# Master_V0_1.net
KiCad netlist of a schematic drawn in EAGLE
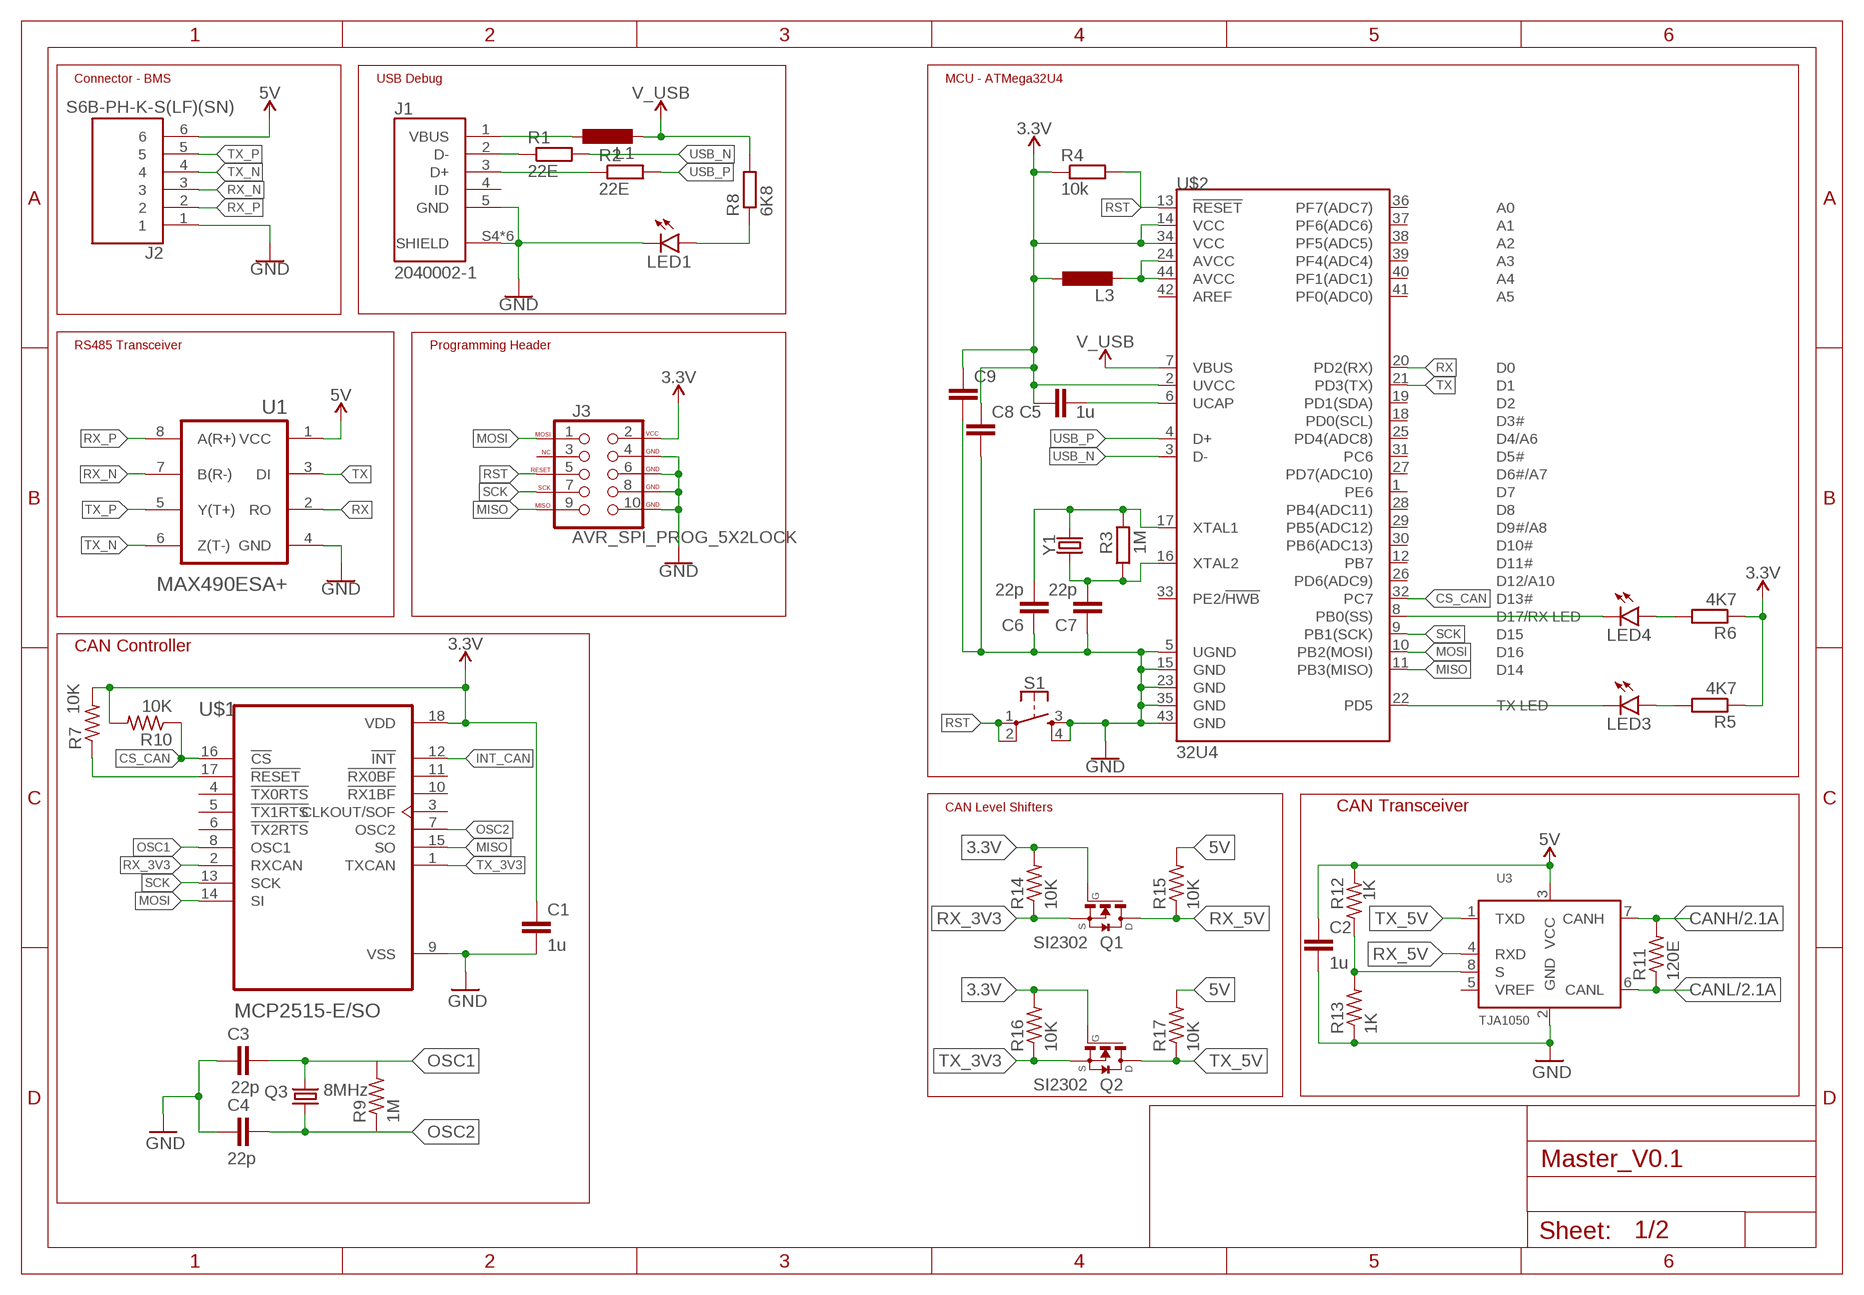
[diagram p0: schematic, sheet 1]
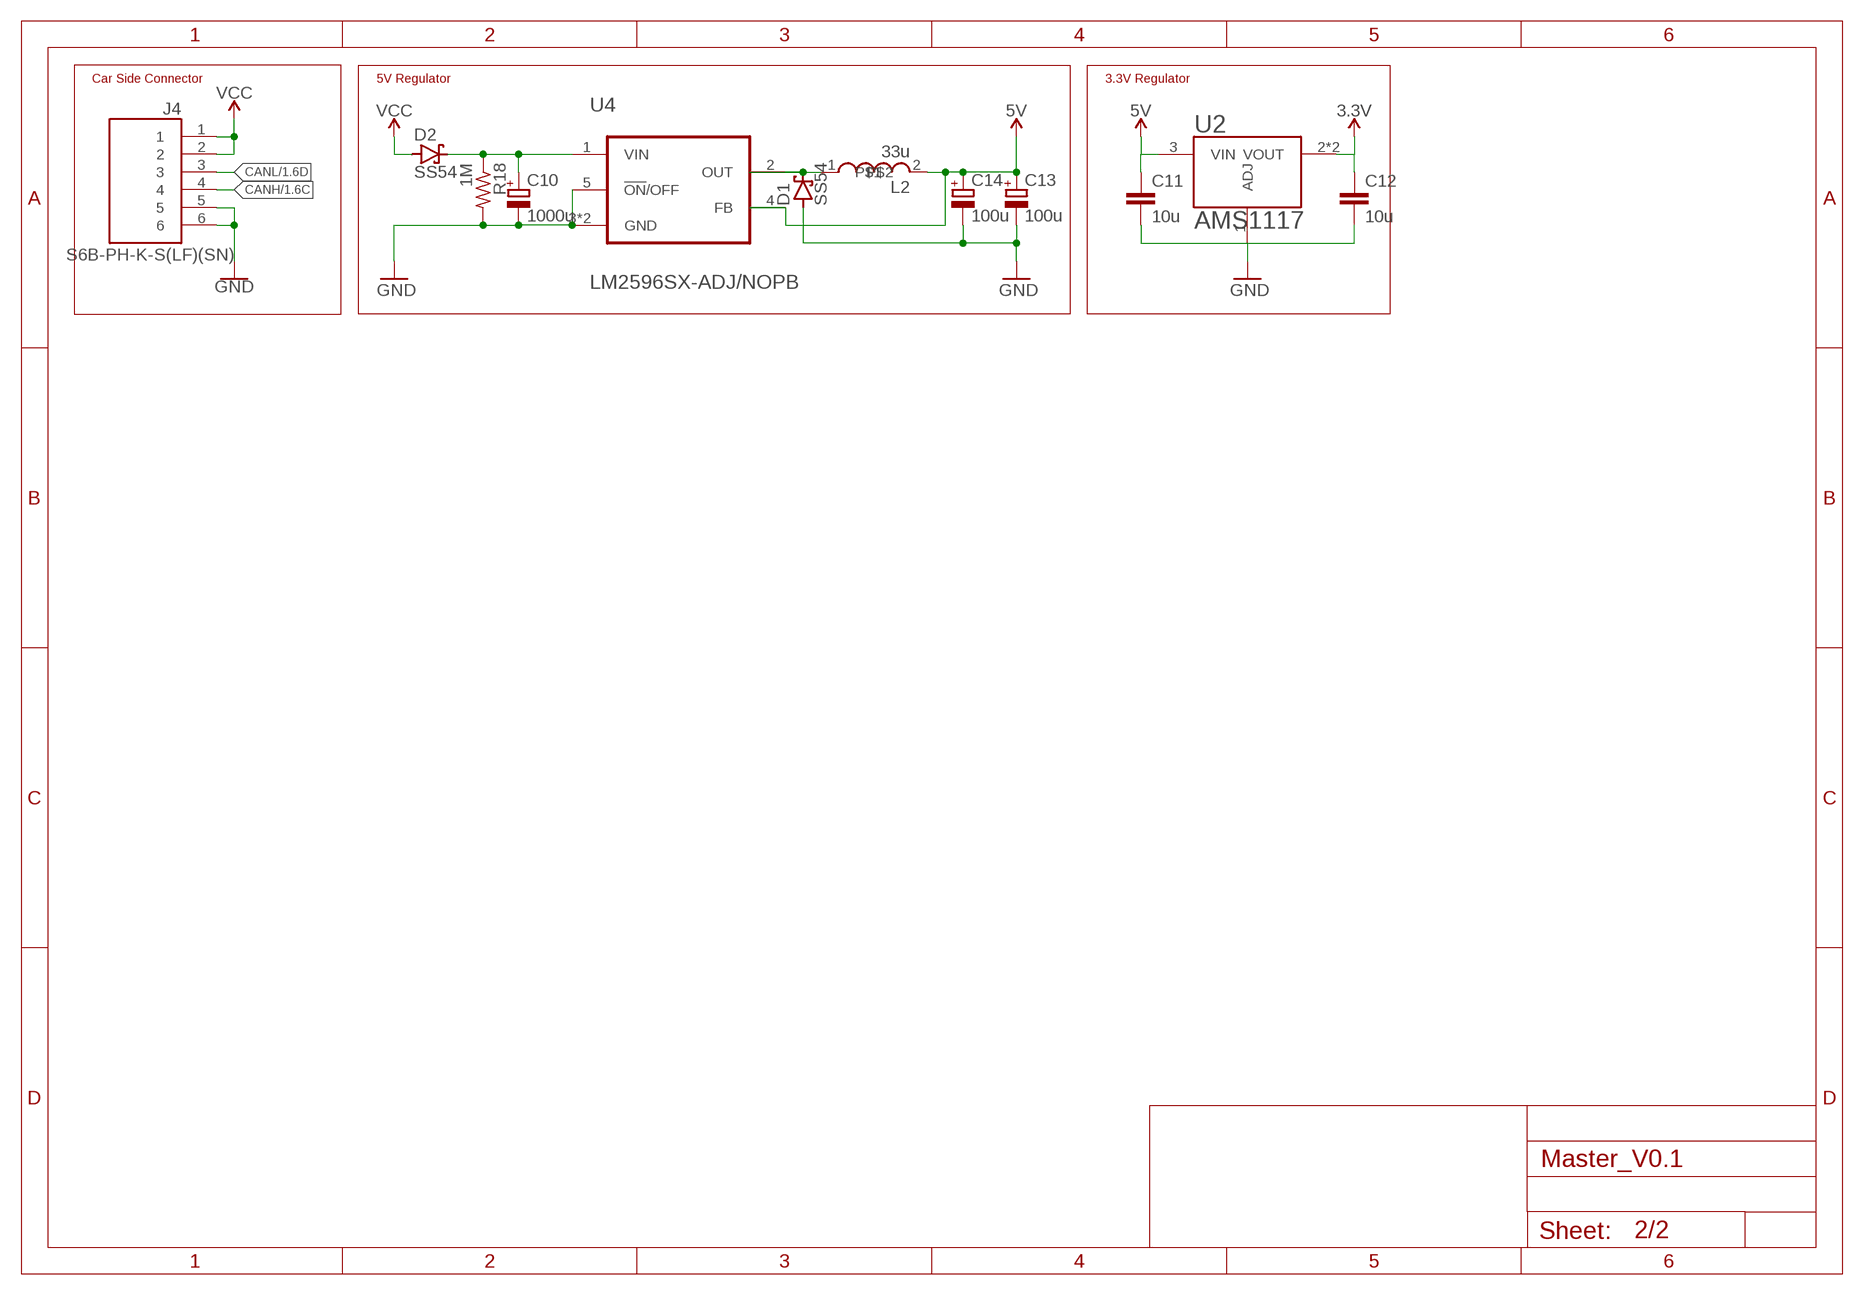
[diagram p1: schematic, sheet 2]

(export (version "E")
  (design (tool "Eeschema 10.0.6"))
  (components
    (comp (ref "C1")
      (value "1u")
      (footprint "eagle-import:C0805")
      (libsource (lib "eagle-import") (part "C-EUC0805"))
    )
    (comp (ref "C2")
      (value "1u")
      (footprint "eagle-import:C0805")
      (libsource (lib "eagle-import") (part "C-EUC0805"))
    )
    (comp (ref "C3")
      (value "22p")
      (footprint "eagle-import:C0805")
      (libsource (lib "eagle-import") (part "C-EUC0805"))
    )
    (comp (ref "C4")
      (value "22p")
      (footprint "eagle-import:C0805")
      (libsource (lib "eagle-import") (part "C-EUC0805"))
    )
    (comp (ref "C5")
      (value "1u")
      (footprint "eagle-import:C0805")
      (libsource (lib "eagle-import") (part "C-EUC0805"))
    )
    (comp (ref "C6")
      (value "22p")
      (footprint "eagle-import:C0805")
      (libsource (lib "eagle-import") (part "C-EUC0805"))
    )
    (comp (ref "C7")
      (value "22p")
      (footprint "eagle-import:C0805")
      (libsource (lib "eagle-import") (part "C-EUC0805"))
    )
    (comp (ref "C8")
      (value "C-EUC0805")
      (footprint "eagle-import:C0805")
      (libsource (lib "eagle-import") (part "C-EUC0805"))
    )
    (comp (ref "C9")
      (value "C-EUC0805")
      (footprint "eagle-import:C0805")
      (libsource (lib "eagle-import") (part "C-EUC0805"))
    )
    (comp (ref "J1")
      (value "2040002-1")
      (footprint "eagle-import:TE_2040002-1")
      (fields (field (name "MF") "TE Connectivity"))
      (libsource (lib "eagle-import") (part "2040002-1"))
    )
    (comp (ref "J2")
      (value "S6B-PH-K-S(LF)(SN)")
      (footprint "eagle-import:JST_S6B-PH-K-S(LF)(SN)")
      (fields (field (name "MF") "JST Sales"))
      (libsource (lib "eagle-import") (part "S6B-PH-K-S(LF)(SN)"))
    )
    (comp (ref "J3")
      (value "AVR_SPI_PROG_5X2LOCK")
      (footprint "eagle-import:2X5-SHROUDED_LOCK")
      (libsource (lib "eagle-import") (part "AVR_SPI_PROG_5X2LOCK"))
    )
    (comp (ref "L1")
      (value "L-EUL2012C")
      (footprint "eagle-import:L2012C")
      (libsource (lib "eagle-import") (part "L-EUL2012C"))
    )
    (comp (ref "L3")
      (value "L-EUL2012C")
      (footprint "eagle-import:L2012C")
      (libsource (lib "eagle-import") (part "L-EUL2012C"))
    )
    (comp (ref "LED1")
      (value "LEDCHIPLED_0805")
      (footprint "eagle-import:CHIPLED_0805")
      (libsource (lib "eagle-import") (part "LEDCHIPLED_0805"))
    )
    (comp (ref "LED3")
      (value "LEDCHIPLED_0805")
      (footprint "eagle-import:CHIPLED_0805")
      (libsource (lib "eagle-import") (part "LEDCHIPLED_0805"))
    )
    (comp (ref "LED4")
      (value "LEDCHIPLED_0805")
      (footprint "eagle-import:CHIPLED_0805")
      (libsource (lib "eagle-import") (part "LEDCHIPLED_0805"))
    )
    (comp (ref "Q1")
      (value "SI2302")
      (footprint "eagle-import:SOT23")
      (fields (field (name "MF") "Vishay Siliconix"))
      (libsource (lib "eagle-import") (part "SI2302"))
    )
    (comp (ref "Q2")
      (value "SI2302")
      (footprint "eagle-import:SOT23")
      (fields (field (name "MF") "Vishay Siliconix"))
      (libsource (lib "eagle-import") (part "SI2302"))
    )
    (comp (ref "Q3")
      (value "8MHz")
      (footprint "eagle-import:HC49_S")
      (libsource (lib "eagle-import") (part "CRYSTALHC49S"))
    )
    (comp (ref "R1")
      (value "22E")
      (footprint "eagle-import:R0805")
      (libsource (lib "eagle-import") (part "R-EU_R0805"))
    )
    (comp (ref "R2")
      (value "22E")
      (footprint "eagle-import:R0805")
      (libsource (lib "eagle-import") (part "R-EU_R0805"))
    )
    (comp (ref "R3")
      (value "1M")
      (footprint "eagle-import:R0805")
      (libsource (lib "eagle-import") (part "R-EU_R0805"))
    )
    (comp (ref "R4")
      (value "10k")
      (footprint "eagle-import:R0805")
      (libsource (lib "eagle-import") (part "R-EU_R0805"))
    )
    (comp (ref "R5")
      (value "4K7")
      (footprint "eagle-import:R0805")
      (libsource (lib "eagle-import") (part "R-EU_R0805"))
    )
    (comp (ref "R6")
      (value "4K7")
      (footprint "eagle-import:R0805")
      (libsource (lib "eagle-import") (part "R-EU_R0805"))
    )
    (comp (ref "R7")
      (value "10K")
      (footprint "eagle-import:R0805")
      (libsource (lib "eagle-import") (part "R-US_R0805"))
    )
    (comp (ref "R8")
      (value "6K8")
      (footprint "eagle-import:R0805")
      (libsource (lib "eagle-import") (part "R-EU_R0805"))
    )
    (comp (ref "R9")
      (value "1M")
      (footprint "eagle-import:R0805")
      (libsource (lib "eagle-import") (part "R-US_R0805"))
    )
    (comp (ref "R10")
      (value "10K")
      (footprint "eagle-import:R0805")
      (libsource (lib "eagle-import") (part "R-US_R0805"))
    )
    (comp (ref "R11")
      (value "120E")
      (footprint "eagle-import:R0805")
      (libsource (lib "eagle-import") (part "R-US_R0805"))
    )
    (comp (ref "R12")
      (value "1K")
      (footprint "eagle-import:R0805")
      (libsource (lib "eagle-import") (part "R-US_R0805"))
    )
    (comp (ref "R13")
      (value "1K")
      (footprint "eagle-import:R0805")
      (libsource (lib "eagle-import") (part "R-US_R0805"))
    )
    (comp (ref "R14")
      (value "10K")
      (footprint "eagle-import:R0805")
      (libsource (lib "eagle-import") (part "R-US_R0805"))
    )
    (comp (ref "R15")
      (value "10K")
      (footprint "eagle-import:R0805")
      (libsource (lib "eagle-import") (part "R-US_R0805"))
    )
    (comp (ref "R16")
      (value "10K")
      (footprint "eagle-import:R0805")
      (libsource (lib "eagle-import") (part "R-US_R0805"))
    )
    (comp (ref "R17")
      (value "10K")
      (footprint "eagle-import:R0805")
      (libsource (lib "eagle-import") (part "R-US_R0805"))
    )
    (comp (ref "S1")
      (value "MOMENTARY-SWITCH-SPST-2-SMD-5.2MM")
      (footprint "eagle-import:TACTILE_SWITCH_SMD_5.2MM")
      (libsource (lib "eagle-import") (part "MOMENTARY-SWITCH-SPST-2-SMD-5.2MM"))
    )
    (comp (ref "U$1")
      (value "MCP2515-E/SO")
      (footprint "eagle-import:SOIC127P1030X265-18N")
      (fields (field (name "MF") "Microchip"))
      (libsource (lib "eagle-import") (part "MCP2515-E/SO"))
    )
    (comp (ref "U$2")
      (value "32U4")
      (footprint "eagle-import:TQFP44")
      (libsource (lib "eagle-import") (part "ATMEGA32U4TQFP-44"))
    )
    (comp (ref "U1")
      (value "MAX490ESA+")
      (footprint "eagle-import:SOIC127P600X175-8N")
      (fields (field (name "MF") "Maxim Integrated"))
      (libsource (lib "eagle-import") (part "MAX490ESA+"))
    )
    (comp (ref "U3")
      (value "TJA1050")
      (footprint "eagle-import:SOT96-1")
      (fields (field (name "MF") "NXP USA"))
      (libsource (lib "eagle-import") (part "TJA1050"))
    )
    (comp (ref "Y1")
      (value "CRYSTALPTH-HC49UV")
      (footprint "eagle-import:HC49U")
      (libsource (lib "eagle-import") (part "CRYSTALPTH-HC49UV"))
    )
    (comp (ref "C10")
      (value "1000u")
      (footprint "eagle-import:E5-10,5")
      (libsource (lib "eagle-import") (part "CPOL-EUE5-10.5"))
    )
    (comp (ref "C11")
      (value "10u")
      (footprint "eagle-import:C0805")
      (libsource (lib "eagle-import") (part "C-EUC0805"))
    )
    (comp (ref "C12")
      (value "10u")
      (footprint "eagle-import:C0805")
      (libsource (lib "eagle-import") (part "C-EUC0805"))
    )
    (comp (ref "C13")
      (value "100u")
      (footprint "eagle-import:E2-4")
      (libsource (lib "eagle-import") (part "CPOL-EUE2-4"))
    )
    (comp (ref "C14")
      (value "100u")
      (footprint "eagle-import:E2-4")
      (libsource (lib "eagle-import") (part "CPOL-EUE2-4"))
    )
    (comp (ref "D1")
      (value "SS54")
      (footprint "eagle-import:SMC")
      (libsource (lib "eagle-import") (part "SCHOTTKY-DIODESMC"))
    )
    (comp (ref "D2")
      (value "SS54")
      (footprint "eagle-import:SMC")
      (libsource (lib "eagle-import") (part "SCHOTTKY-DIODESMC"))
    )
    (comp (ref "J4")
      (value "S6B-PH-K-S(LF)(SN)")
      (footprint "eagle-import:JST_S6B-PH-K-S(LF)(SN)")
      (fields (field (name "MF") "JST Sales"))
      (libsource (lib "eagle-import") (part "S6B-PH-K-S(LF)(SN)"))
    )
    (comp (ref "L2")
      (value "33u")
      (footprint "eagle-import:CDRH127_LD")
      (libsource (lib "eagle-import") (part "CDRH127/LDCDRH/LD"))
    )
    (comp (ref "R18")
      (value "1M")
      (footprint "eagle-import:R0805")
      (libsource (lib "eagle-import") (part "R-US_R0805"))
    )
    (comp (ref "U2")
      (value "AMS1117")
      (footprint "eagle-import:SOT230P700X170-4")
      (fields (field (name "MF") "Advanced Monolithic Systems, Inc."))
      (libsource (lib "eagle-import") (part "AMS1117"))
    )
    (comp (ref "U4")
      (value "LM2596SX-ADJ/NOPB")
      (footprint "eagle-import:VREG_LM2596SX-ADJ_NOPB")
      (fields (field (name "MF") "Texas Instruments"))
      (libsource (lib "eagle-import") (part "LM2596SX-ADJ/NOPB"))
    )
  )
  (nets
    (net (code "1") (name "3.3V") (class "Default")
      (node (ref "C1") (pin "1") (pinfunction "1_1") (pintype "passive"))
      (node (ref "C12") (pin "1") (pinfunction "1_1") (pintype "passive"))
      (node (ref "C5") (pin "1") (pinfunction "1_1") (pintype "passive"))
      (node (ref "C8") (pin "1") (pinfunction "1_1") (pintype "passive"))
      (node (ref "C9") (pin "1") (pinfunction "1_1") (pintype "passive"))
      (node (ref "J3") (pin "2") (pinfunction "VCC_2") (pintype "power_in"))
      (node (ref "L3") (pin "1") (pinfunction "1_1") (pintype "passive"))
      (node (ref "Q1") (pin "1") (pinfunction "G_1") (pintype "passive"))
      (node (ref "Q2") (pin "1") (pinfunction "G_1") (pintype "passive"))
      (node (ref "R10") (pin "2") (pinfunction "2_2") (pintype "passive"))
      (node (ref "R14") (pin "2") (pinfunction "2_2") (pintype "passive"))
      (node (ref "R16") (pin "2") (pinfunction "2_2") (pintype "passive"))
      (node (ref "R4") (pin "1") (pinfunction "1_1") (pintype "passive"))
      (node (ref "R5") (pin "1") (pinfunction "1_1") (pintype "passive"))
      (node (ref "R6") (pin "1") (pinfunction "1_1") (pintype "passive"))
      (node (ref "R7") (pin "2") (pinfunction "2_2") (pintype "passive"))
      (node (ref "U$1") (pin "18") (pinfunction "VDD_18") (pintype "power_in"))
      (node (ref "U$2") (pin "14") (pinfunction "VCC_14") (pintype "bidirectional"))
      (node (ref "U$2") (pin "2") (pinfunction "UVCC_2") (pintype "bidirectional"))
      (node (ref "U$2") (pin "34") (pinfunction "VCC_34") (pintype "bidirectional"))
      (node (ref "U2") (pin "2") (pinfunction "VOUT_2") (pintype "output"))
      (node (ref "U2") (pin "4") (pinfunction "VOUT_4") (pintype "output"))
    )
    (net (code "2") (name "5V") (class "Default")
      (node (ref "C11") (pin "1") (pinfunction "1_1") (pintype "passive"))
      (node (ref "C13") (pin "+") (pinfunction "+_+") (pintype "passive"))
      (node (ref "C14") (pin "+") (pinfunction "+_+") (pintype "passive"))
      (node (ref "C2") (pin "1") (pinfunction "1_1") (pintype "passive"))
      (node (ref "J2") (pin "6") (pinfunction "6_6") (pintype "passive"))
      (node (ref "L2") (pin "2") (pinfunction "P$2_2") (pintype "bidirectional"))
      (node (ref "R12") (pin "2") (pinfunction "2_2") (pintype "passive"))
      (node (ref "R15") (pin "2") (pinfunction "2_2") (pintype "passive"))
      (node (ref "R17") (pin "2") (pinfunction "2_2") (pintype "passive"))
      (node (ref "U1") (pin "1") (pinfunction "VCC_1") (pintype "power_in"))
      (node (ref "U2") (pin "3") (pinfunction "VIN_3") (pintype "input"))
      (node (ref "U3") (pin "3") (pinfunction "VCC_3") (pintype "bidirectional"))
      (node (ref "U4") (pin "4") (pinfunction "FB_4") (pintype "input"))
    )
    (net (code "3") (name "CANH") (class "Default")
      (node (ref "J4") (pin "4") (pinfunction "4_4") (pintype "passive"))
      (node (ref "R11") (pin "2") (pinfunction "2_2") (pintype "passive"))
      (node (ref "U3") (pin "7") (pinfunction "CANH_7") (pintype "bidirectional"))
    )
    (net (code "4") (name "CANL") (class "Default")
      (node (ref "J4") (pin "3") (pinfunction "3_3") (pintype "passive"))
      (node (ref "R11") (pin "1") (pinfunction "1_1") (pintype "passive"))
      (node (ref "U3") (pin "6") (pinfunction "CANL_6") (pintype "bidirectional"))
    )
    (net (code "5") (name "CS_CAN") (class "Default")
      (node (ref "R10") (pin "1") (pinfunction "1_1") (pintype "passive"))
      (node (ref "U$1") (pin "16") (pinfunction "~{CS}_16") (pintype "input"))
      (node (ref "U$2") (pin "32") (pinfunction "PC7_32") (pintype "bidirectional"))
    )
    (net (code "6") (name "GND") (class "Default")
      (node (ref "C1") (pin "2") (pinfunction "2_2") (pintype "passive"))
      (node (ref "C10") (pin "-") (pinfunction "-_-") (pintype "passive"))
      (node (ref "C11") (pin "2") (pinfunction "2_2") (pintype "passive"))
      (node (ref "C12") (pin "2") (pinfunction "2_2") (pintype "passive"))
      (node (ref "C13") (pin "-") (pinfunction "-_-") (pintype "passive"))
      (node (ref "C14") (pin "-") (pinfunction "-_-") (pintype "passive"))
      (node (ref "C2") (pin "2") (pinfunction "2_2") (pintype "passive"))
      (node (ref "C3") (pin "1") (pinfunction "1_1") (pintype "passive"))
      (node (ref "C4") (pin "1") (pinfunction "1_1") (pintype "passive"))
      (node (ref "C6") (pin "1") (pinfunction "1_1") (pintype "passive"))
      (node (ref "C7") (pin "1") (pinfunction "1_1") (pintype "passive"))
      (node (ref "C8") (pin "2") (pinfunction "2_2") (pintype "passive"))
      (node (ref "C9") (pin "2") (pinfunction "2_2") (pintype "passive"))
      (node (ref "D1") (pin "A") (pinfunction "A_A") (pintype "passive"))
      (node (ref "J1") (pin "5") (pinfunction "GND_5") (pintype "power_in"))
      (node (ref "J1") (pin "S4") (pinfunction "SHIELD_S4") (pintype "power_in"))
      (node (ref "J1") (pin "S5") (pinfunction "SHIELD_S5") (pintype "power_in"))
      (node (ref "J1") (pin "SH1") (pinfunction "SHIELD_SH1") (pintype "power_in"))
      (node (ref "J1") (pin "SH2") (pinfunction "SHIELD_SH2") (pintype "power_in"))
      (node (ref "J1") (pin "SH3") (pinfunction "SHIELD_SH3") (pintype "power_in"))
      (node (ref "J1") (pin "SH4") (pinfunction "SHIELD_SH4") (pintype "power_in"))
      (node (ref "J2") (pin "1") (pinfunction "1_1") (pintype "passive"))
      (node (ref "J3") (pin "10") (pinfunction "GND_10") (pintype "power_in"))
      (node (ref "J3") (pin "4") (pinfunction "GND_4") (pintype "power_in"))
      (node (ref "J3") (pin "6") (pinfunction "GND_6") (pintype "power_in"))
      (node (ref "J3") (pin "8") (pinfunction "GND_8") (pintype "power_in"))
      (node (ref "J4") (pin "5") (pinfunction "5_5") (pintype "passive"))
      (node (ref "J4") (pin "6") (pinfunction "6_6") (pintype "passive"))
      (node (ref "LED1") (pin "C") (pinfunction "C_C") (pintype "passive"))
      (node (ref "R13") (pin "1") (pinfunction "1_1") (pintype "passive"))
      (node (ref "R18") (pin "2") (pinfunction "2_2") (pintype "passive"))
      (node (ref "S1") (pin "3") (pinfunction "3_3") (pintype "passive"))
      (node (ref "S1") (pin "4") (pinfunction "4_4") (pintype "passive"))
      (node (ref "U$1") (pin "9") (pinfunction "VSS_9") (pintype "power_in"))
      (node (ref "U$2") (pin "15") (pinfunction "GND_15") (pintype "bidirectional"))
      (node (ref "U$2") (pin "23") (pinfunction "GND_23") (pintype "bidirectional"))
      (node (ref "U$2") (pin "35") (pinfunction "GND_35") (pintype "bidirectional"))
      (node (ref "U$2") (pin "43") (pinfunction "GND_43") (pintype "bidirectional"))
      (node (ref "U$2") (pin "5") (pinfunction "UGND_5") (pintype "bidirectional"))
      (node (ref "U1") (pin "4") (pinfunction "GND_4") (pintype "power_in"))
      (node (ref "U2") (pin "1") (pinfunction "ADJ_1") (pintype "power_in"))
      (node (ref "U3") (pin "2") (pinfunction "GND_2") (pintype "bidirectional"))
      (node (ref "U4") (pin "3") (pinfunction "GND_3") (pintype "power_in"))
      (node (ref "U4") (pin "5") (pinfunction "~{ON}/OFF_5") (pintype "input"))
      (node (ref "U4") (pin "6") (pinfunction "GND_6") (pintype "power_in"))
    )
    (net (code "7") (name "INT_CAN") (class "Default")
      (node (ref "U$1") (pin "12") (pinfunction "~{INT}_12") (pintype "output"))
    )
    (net (code "8") (name "MISO") (class "Default")
      (node (ref "J3") (pin "9") (pinfunction "MISO_9") (pintype "passive"))
      (node (ref "U$1") (pin "15") (pinfunction "SO_15") (pintype "output"))
      (node (ref "U$2") (pin "11") (pinfunction "PB3(MISO)_11") (pintype "bidirectional"))
    )
    (net (code "9") (name "MOSI") (class "Default")
      (node (ref "J3") (pin "1") (pinfunction "MOSI_1") (pintype "passive"))
      (node (ref "U$1") (pin "14") (pinfunction "SI_14") (pintype "input"))
      (node (ref "U$2") (pin "10") (pinfunction "PB2(MOSI)_10") (pintype "bidirectional"))
    )
    (net (code "10") (name "Net-(J1-D+)") (class "Default")
      (node (ref "J1") (pin "3") (pinfunction "D+_3") (pintype "bidirectional"))
      (node (ref "R2") (pin "1") (pinfunction "1_1") (pintype "passive"))
    )
    (net (code "11") (name "Net-(J1-D-)") (class "Default")
      (node (ref "J1") (pin "2") (pinfunction "D-_2") (pintype "bidirectional"))
      (node (ref "R1") (pin "1") (pinfunction "1_1") (pintype "passive"))
    )
    (net (code "12") (name "Net-(J1-VBUS)") (class "Default")
      (node (ref "J1") (pin "1") (pinfunction "VBUS_1") (pintype "power_in"))
      (node (ref "L1") (pin "1") (pinfunction "1_1") (pintype "passive"))
    )
    (net (code "13") (name "Net-(L2-P$1)") (class "Default")
      (node (ref "D1") (pin "C") (pinfunction "C_C") (pintype "passive"))
      (node (ref "L2") (pin "1") (pinfunction "P$1_1") (pintype "bidirectional"))
      (node (ref "U4") (pin "2") (pinfunction "OUT_2") (pintype "output"))
    )
    (net (code "14") (name "Net-(L3-Pad2)") (class "Default")
      (node (ref "L3") (pin "2") (pinfunction "2_2") (pintype "passive"))
      (node (ref "U$2") (pin "24") (pinfunction "AVCC_24") (pintype "bidirectional"))
      (node (ref "U$2") (pin "44") (pinfunction "AVCC_44") (pintype "bidirectional"))
    )
    (net (code "15") (name "Net-(LED1-PadA)") (class "Default")
      (node (ref "LED1") (pin "A") (pinfunction "A_A") (pintype "passive"))
      (node (ref "R8") (pin "1") (pinfunction "1_1") (pintype "passive"))
    )
    (net (code "16") (name "Net-(LED3-PadA)") (class "Default")
      (node (ref "LED3") (pin "A") (pinfunction "A_A") (pintype "passive"))
      (node (ref "R5") (pin "2") (pinfunction "2_2") (pintype "passive"))
    )
    (net (code "17") (name "Net-(LED4-PadA)") (class "Default")
      (node (ref "LED4") (pin "A") (pinfunction "A_A") (pintype "passive"))
      (node (ref "R6") (pin "2") (pinfunction "2_2") (pintype "passive"))
    )
    (net (code "18") (name "Net-(U$1-~{RESET})") (class "Default")
      (node (ref "R7") (pin "1") (pinfunction "1_1") (pintype "passive"))
      (node (ref "U$1") (pin "17") (pinfunction "~{RESET}_17") (pintype "input"))
    )
    (net (code "19") (name "Net-(U$2-PB0(SS))") (class "Default")
      (node (ref "LED4") (pin "C") (pinfunction "C_C") (pintype "passive"))
      (node (ref "U$2") (pin "8") (pinfunction "PB0(SS)_8") (pintype "bidirectional"))
    )
    (net (code "20") (name "Net-(U$2-PD5)") (class "Default")
      (node (ref "LED3") (pin "C") (pinfunction "C_C") (pintype "passive"))
      (node (ref "U$2") (pin "22") (pinfunction "PD5_22") (pintype "bidirectional"))
    )
    (net (code "21") (name "Net-(U$2-UCAP)") (class "Default")
      (node (ref "C5") (pin "2") (pinfunction "2_2") (pintype "passive"))
      (node (ref "U$2") (pin "6") (pinfunction "UCAP_6") (pintype "bidirectional"))
    )
    (net (code "22") (name "Net-(U$2-XTAL1)") (class "Default")
      (node (ref "C6") (pin "2") (pinfunction "2_2") (pintype "passive"))
      (node (ref "R3") (pin "2") (pinfunction "2_2") (pintype "passive"))
      (node (ref "U$2") (pin "17") (pinfunction "XTAL1_17") (pintype "bidirectional"))
      (node (ref "Y1") (pin "2") (pinfunction "2_2") (pintype "passive"))
    )
    (net (code "23") (name "Net-(U$2-XTAL2)") (class "Default")
      (node (ref "C7") (pin "2") (pinfunction "2_2") (pintype "passive"))
      (node (ref "R3") (pin "1") (pinfunction "1_1") (pintype "passive"))
      (node (ref "U$2") (pin "16") (pinfunction "XTAL2_16") (pintype "bidirectional"))
      (node (ref "Y1") (pin "1") (pinfunction "1_1") (pintype "passive"))
    )
    (net (code "24") (name "Net-(U3-S)") (class "Default")
      (node (ref "R12") (pin "1") (pinfunction "1_1") (pintype "passive"))
      (node (ref "R13") (pin "2") (pinfunction "2_2") (pintype "passive"))
      (node (ref "U3") (pin "8") (pinfunction "S_8") (pintype "power_in"))
    )
    (net (code "25") (name "Net-(U4-VIN)") (class "Default")
      (node (ref "C10") (pin "+") (pinfunction "+_+") (pintype "passive"))
      (node (ref "D2") (pin "C") (pinfunction "C_C") (pintype "passive"))
      (node (ref "R18") (pin "1") (pinfunction "1_1") (pintype "passive"))
      (node (ref "U4") (pin "1") (pinfunction "VIN_1") (pintype "input"))
    )
    (net (code "26") (name "OSC1") (class "Default")
      (node (ref "C3") (pin "2") (pinfunction "2_2") (pintype "passive"))
      (node (ref "Q3") (pin "2") (pinfunction "2_2") (pintype "passive"))
      (node (ref "R9") (pin "2") (pinfunction "2_2") (pintype "passive"))
      (node (ref "U$1") (pin "8") (pinfunction "OSC1_8") (pintype "input"))
    )
    (net (code "27") (name "OSC2") (class "Default")
      (node (ref "C4") (pin "2") (pinfunction "2_2") (pintype "passive"))
      (node (ref "Q3") (pin "1") (pinfunction "1_1") (pintype "passive"))
      (node (ref "R9") (pin "1") (pinfunction "1_1") (pintype "passive"))
      (node (ref "U$1") (pin "7") (pinfunction "OSC2_7") (pintype "output"))
    )
    (net (code "28") (name "RST") (class "Default")
      (node (ref "J3") (pin "5") (pinfunction "RESET_5") (pintype "passive"))
      (node (ref "R4") (pin "2") (pinfunction "2_2") (pintype "passive"))
      (node (ref "S1") (pin "1") (pinfunction "1_1") (pintype "passive"))
      (node (ref "S1") (pin "2") (pinfunction "2_2") (pintype "passive"))
      (node (ref "U$2") (pin "13") (pinfunction "~{RESET}_13") (pintype "bidirectional"))
    )
    (net (code "29") (name "RX") (class "Default")
      (node (ref "U$2") (pin "20") (pinfunction "PD2(RX)_20") (pintype "bidirectional"))
      (node (ref "U1") (pin "2") (pinfunction "RO_2") (pintype "output"))
    )
    (net (code "30") (name "RX_3V3") (class "Default")
      (node (ref "Q1") (pin "2") (pinfunction "S_2") (pintype "passive"))
      (node (ref "R14") (pin "1") (pinfunction "1_1") (pintype "passive"))
      (node (ref "U$1") (pin "2") (pinfunction "RXCAN_2") (pintype "input"))
    )
    (net (code "31") (name "RX_5V") (class "Default")
      (node (ref "Q1") (pin "3") (pinfunction "D_3") (pintype "passive"))
      (node (ref "R15") (pin "1") (pinfunction "1_1") (pintype "passive"))
      (node (ref "U3") (pin "4") (pinfunction "RXD_4") (pintype "bidirectional"))
    )
    (net (code "32") (name "RX_N") (class "Default")
      (node (ref "J2") (pin "3") (pinfunction "3_3") (pintype "passive"))
      (node (ref "U1") (pin "7") (pinfunction "B(R-)_7") (pintype "bidirectional"))
    )
    (net (code "33") (name "RX_P") (class "Default")
      (node (ref "J2") (pin "2") (pinfunction "2_2") (pintype "passive"))
      (node (ref "U1") (pin "8") (pinfunction "A(R+)_8") (pintype "bidirectional"))
    )
    (net (code "34") (name "SCK") (class "Default")
      (node (ref "J3") (pin "7") (pinfunction "SCK_7") (pintype "passive"))
      (node (ref "U$1") (pin "13") (pinfunction "SCK_13") (pintype "input"))
      (node (ref "U$2") (pin "9") (pinfunction "PB1(SCK)_9") (pintype "bidirectional"))
    )
    (net (code "35") (name "TX") (class "Default")
      (node (ref "U$2") (pin "21") (pinfunction "PD3(TX)_21") (pintype "bidirectional"))
      (node (ref "U1") (pin "3") (pinfunction "DI_3") (pintype "input"))
    )
    (net (code "36") (name "TX_3V3") (class "Default")
      (node (ref "Q2") (pin "2") (pinfunction "S_2") (pintype "passive"))
      (node (ref "R16") (pin "1") (pinfunction "1_1") (pintype "passive"))
      (node (ref "U$1") (pin "1") (pinfunction "TXCAN_1") (pintype "output"))
    )
    (net (code "37") (name "TX_5V") (class "Default")
      (node (ref "Q2") (pin "3") (pinfunction "D_3") (pintype "passive"))
      (node (ref "R17") (pin "1") (pinfunction "1_1") (pintype "passive"))
      (node (ref "U3") (pin "1") (pinfunction "TXD_1") (pintype "output"))
    )
    (net (code "38") (name "TX_N") (class "Default")
      (node (ref "J2") (pin "4") (pinfunction "4_4") (pintype "passive"))
      (node (ref "U1") (pin "6") (pinfunction "Z(T-)_6") (pintype "bidirectional"))
    )
    (net (code "39") (name "TX_P") (class "Default")
      (node (ref "J2") (pin "5") (pinfunction "5_5") (pintype "passive"))
      (node (ref "U1") (pin "5") (pinfunction "Y(T+)_5") (pintype "bidirectional"))
    )
    (net (code "40") (name "USB_N") (class "Default")
      (node (ref "R1") (pin "2") (pinfunction "2_2") (pintype "passive"))
      (node (ref "U$2") (pin "3") (pinfunction "D-_3") (pintype "bidirectional"))
    )
    (net (code "41") (name "USB_P") (class "Default")
      (node (ref "R2") (pin "2") (pinfunction "2_2") (pintype "passive"))
      (node (ref "U$2") (pin "4") (pinfunction "D+_4") (pintype "bidirectional"))
    )
    (net (code "42") (name "VCC") (class "Default")
      (node (ref "D2") (pin "A") (pinfunction "A_A") (pintype "passive"))
      (node (ref "J4") (pin "1") (pinfunction "1_1") (pintype "passive"))
      (node (ref "J4") (pin "2") (pinfunction "2_2") (pintype "passive"))
    )
    (net (code "43") (name "V_USB") (class "Default")
      (node (ref "L1") (pin "2") (pinfunction "2_2") (pintype "passive"))
      (node (ref "R8") (pin "2") (pinfunction "2_2") (pintype "passive"))
      (node (ref "U$2") (pin "7") (pinfunction "VBUS_7") (pintype "bidirectional"))
    )
    (net (code "44") (name "unconnected-(J1-ID-Pad4)") (class "Default")
      (node (ref "J1") (pin "4") (pinfunction "ID_4") (pintype "bidirectional"))
    )
    (net (code "45") (name "unconnected-(J3-NC-Pad3)") (class "Default")
      (node (ref "J3") (pin "3") (pinfunction "NC_3") (pintype "no_connect"))
    )
    (net (code "46") (name "unconnected-(U$1-CLKOUT{slash}SOF-Pad3)") (class "Default")
      (node (ref "U$1") (pin "3") (pinfunction "CLKOUT/SOF_3") (pintype "output"))
    )
    (net (code "47") (name "unconnected-(U$1-~{RX0BF}-Pad11)") (class "Default")
      (node (ref "U$1") (pin "11") (pinfunction "~{RX0BF}_11") (pintype "output"))
    )
    (net (code "48") (name "unconnected-(U$1-~{RX1BF}-Pad10)") (class "Default")
      (node (ref "U$1") (pin "10") (pinfunction "~{RX1BF}_10") (pintype "output"))
    )
    (net (code "49") (name "unconnected-(U$1-~{TX0RTS}-Pad4)") (class "Default")
      (node (ref "U$1") (pin "4") (pinfunction "~{TX0RTS}_4") (pintype "input"))
    )
    (net (code "50") (name "unconnected-(U$1-~{TX1RTS}-Pad5)") (class "Default")
      (node (ref "U$1") (pin "5") (pinfunction "~{TX1RTS}_5") (pintype "input"))
    )
    (net (code "51") (name "unconnected-(U$1-~{TX2RTS}-Pad6)") (class "Default")
      (node (ref "U$1") (pin "6") (pinfunction "~{TX2RTS}_6") (pintype "input"))
    )
    (net (code "52") (name "unconnected-(U$2-AREF-Pad42)") (class "Default")
      (node (ref "U$2") (pin "42") (pinfunction "AREF_42") (pintype "bidirectional"))
    )
    (net (code "53") (name "unconnected-(U$2-PB4(ADC11)-Pad28)") (class "Default")
      (node (ref "U$2") (pin "28") (pinfunction "PB4(ADC11)_28") (pintype "bidirectional"))
    )
    (net (code "54") (name "unconnected-(U$2-PB5(ADC12)-Pad29)") (class "Default")
      (node (ref "U$2") (pin "29") (pinfunction "PB5(ADC12)_29") (pintype "bidirectional"))
    )
    (net (code "55") (name "unconnected-(U$2-PB6(ADC13)-Pad30)") (class "Default")
      (node (ref "U$2") (pin "30") (pinfunction "PB6(ADC13)_30") (pintype "bidirectional"))
    )
    (net (code "56") (name "unconnected-(U$2-PB7-Pad12)") (class "Default")
      (node (ref "U$2") (pin "12") (pinfunction "PB7_12") (pintype "bidirectional"))
    )
    (net (code "57") (name "unconnected-(U$2-PC6-Pad31)") (class "Default")
      (node (ref "U$2") (pin "31") (pinfunction "PC6_31") (pintype "bidirectional"))
    )
    (net (code "58") (name "unconnected-(U$2-PD0(SCL)-Pad18)") (class "Default")
      (node (ref "U$2") (pin "18") (pinfunction "PD0(SCL)_18") (pintype "bidirectional"))
    )
    (net (code "59") (name "unconnected-(U$2-PD1(SDA)-Pad19)") (class "Default")
      (node (ref "U$2") (pin "19") (pinfunction "PD1(SDA)_19") (pintype "bidirectional"))
    )
    (net (code "60") (name "unconnected-(U$2-PD4(ADC8)-Pad25)") (class "Default")
      (node (ref "U$2") (pin "25") (pinfunction "PD4(ADC8)_25") (pintype "bidirectional"))
    )
    (net (code "61") (name "unconnected-(U$2-PD6(ADC9)-Pad26)") (class "Default")
      (node (ref "U$2") (pin "26") (pinfunction "PD6(ADC9)_26") (pintype "bidirectional"))
    )
    (net (code "62") (name "unconnected-(U$2-PD7(ADC10)-Pad27)") (class "Default")
      (node (ref "U$2") (pin "27") (pinfunction "PD7(ADC10)_27") (pintype "bidirectional"))
    )
    (net (code "63") (name "unconnected-(U$2-PE2{slash}~{HWB}-Pad33)") (class "Default")
      (node (ref "U$2") (pin "33") (pinfunction "PE2/~{HWB}_33") (pintype "bidirectional"))
    )
    (net (code "64") (name "unconnected-(U$2-PE6-Pad1)") (class "Default")
      (node (ref "U$2") (pin "1") (pinfunction "PE6_1") (pintype "bidirectional"))
    )
    (net (code "65") (name "unconnected-(U$2-PF0(ADC0)-Pad41)") (class "Default")
      (node (ref "U$2") (pin "41") (pinfunction "PF0(ADC0)_41") (pintype "bidirectional"))
    )
    (net (code "66") (name "unconnected-(U$2-PF1(ADC1)-Pad40)") (class "Default")
      (node (ref "U$2") (pin "40") (pinfunction "PF1(ADC1)_40") (pintype "bidirectional"))
    )
    (net (code "67") (name "unconnected-(U$2-PF4(ADC4)-Pad39)") (class "Default")
      (node (ref "U$2") (pin "39") (pinfunction "PF4(ADC4)_39") (pintype "bidirectional"))
    )
    (net (code "68") (name "unconnected-(U$2-PF5(ADC5)-Pad38)") (class "Default")
      (node (ref "U$2") (pin "38") (pinfunction "PF5(ADC5)_38") (pintype "bidirectional"))
    )
    (net (code "69") (name "unconnected-(U$2-PF6(ADC6)-Pad37)") (class "Default")
      (node (ref "U$2") (pin "37") (pinfunction "PF6(ADC6)_37") (pintype "bidirectional"))
    )
    (net (code "70") (name "unconnected-(U$2-PF7(ADC7)-Pad36)") (class "Default")
      (node (ref "U$2") (pin "36") (pinfunction "PF7(ADC7)_36") (pintype "bidirectional"))
    )
    (net (code "71") (name "unconnected-(U3-VREF-Pad5)") (class "Default")
      (node (ref "U3") (pin "5") (pinfunction "VREF_5") (pintype "passive"))
    )
  )
)
